# MOSFET_Connections.net
KiCad netlist of a schematic drawn in Altium Designer
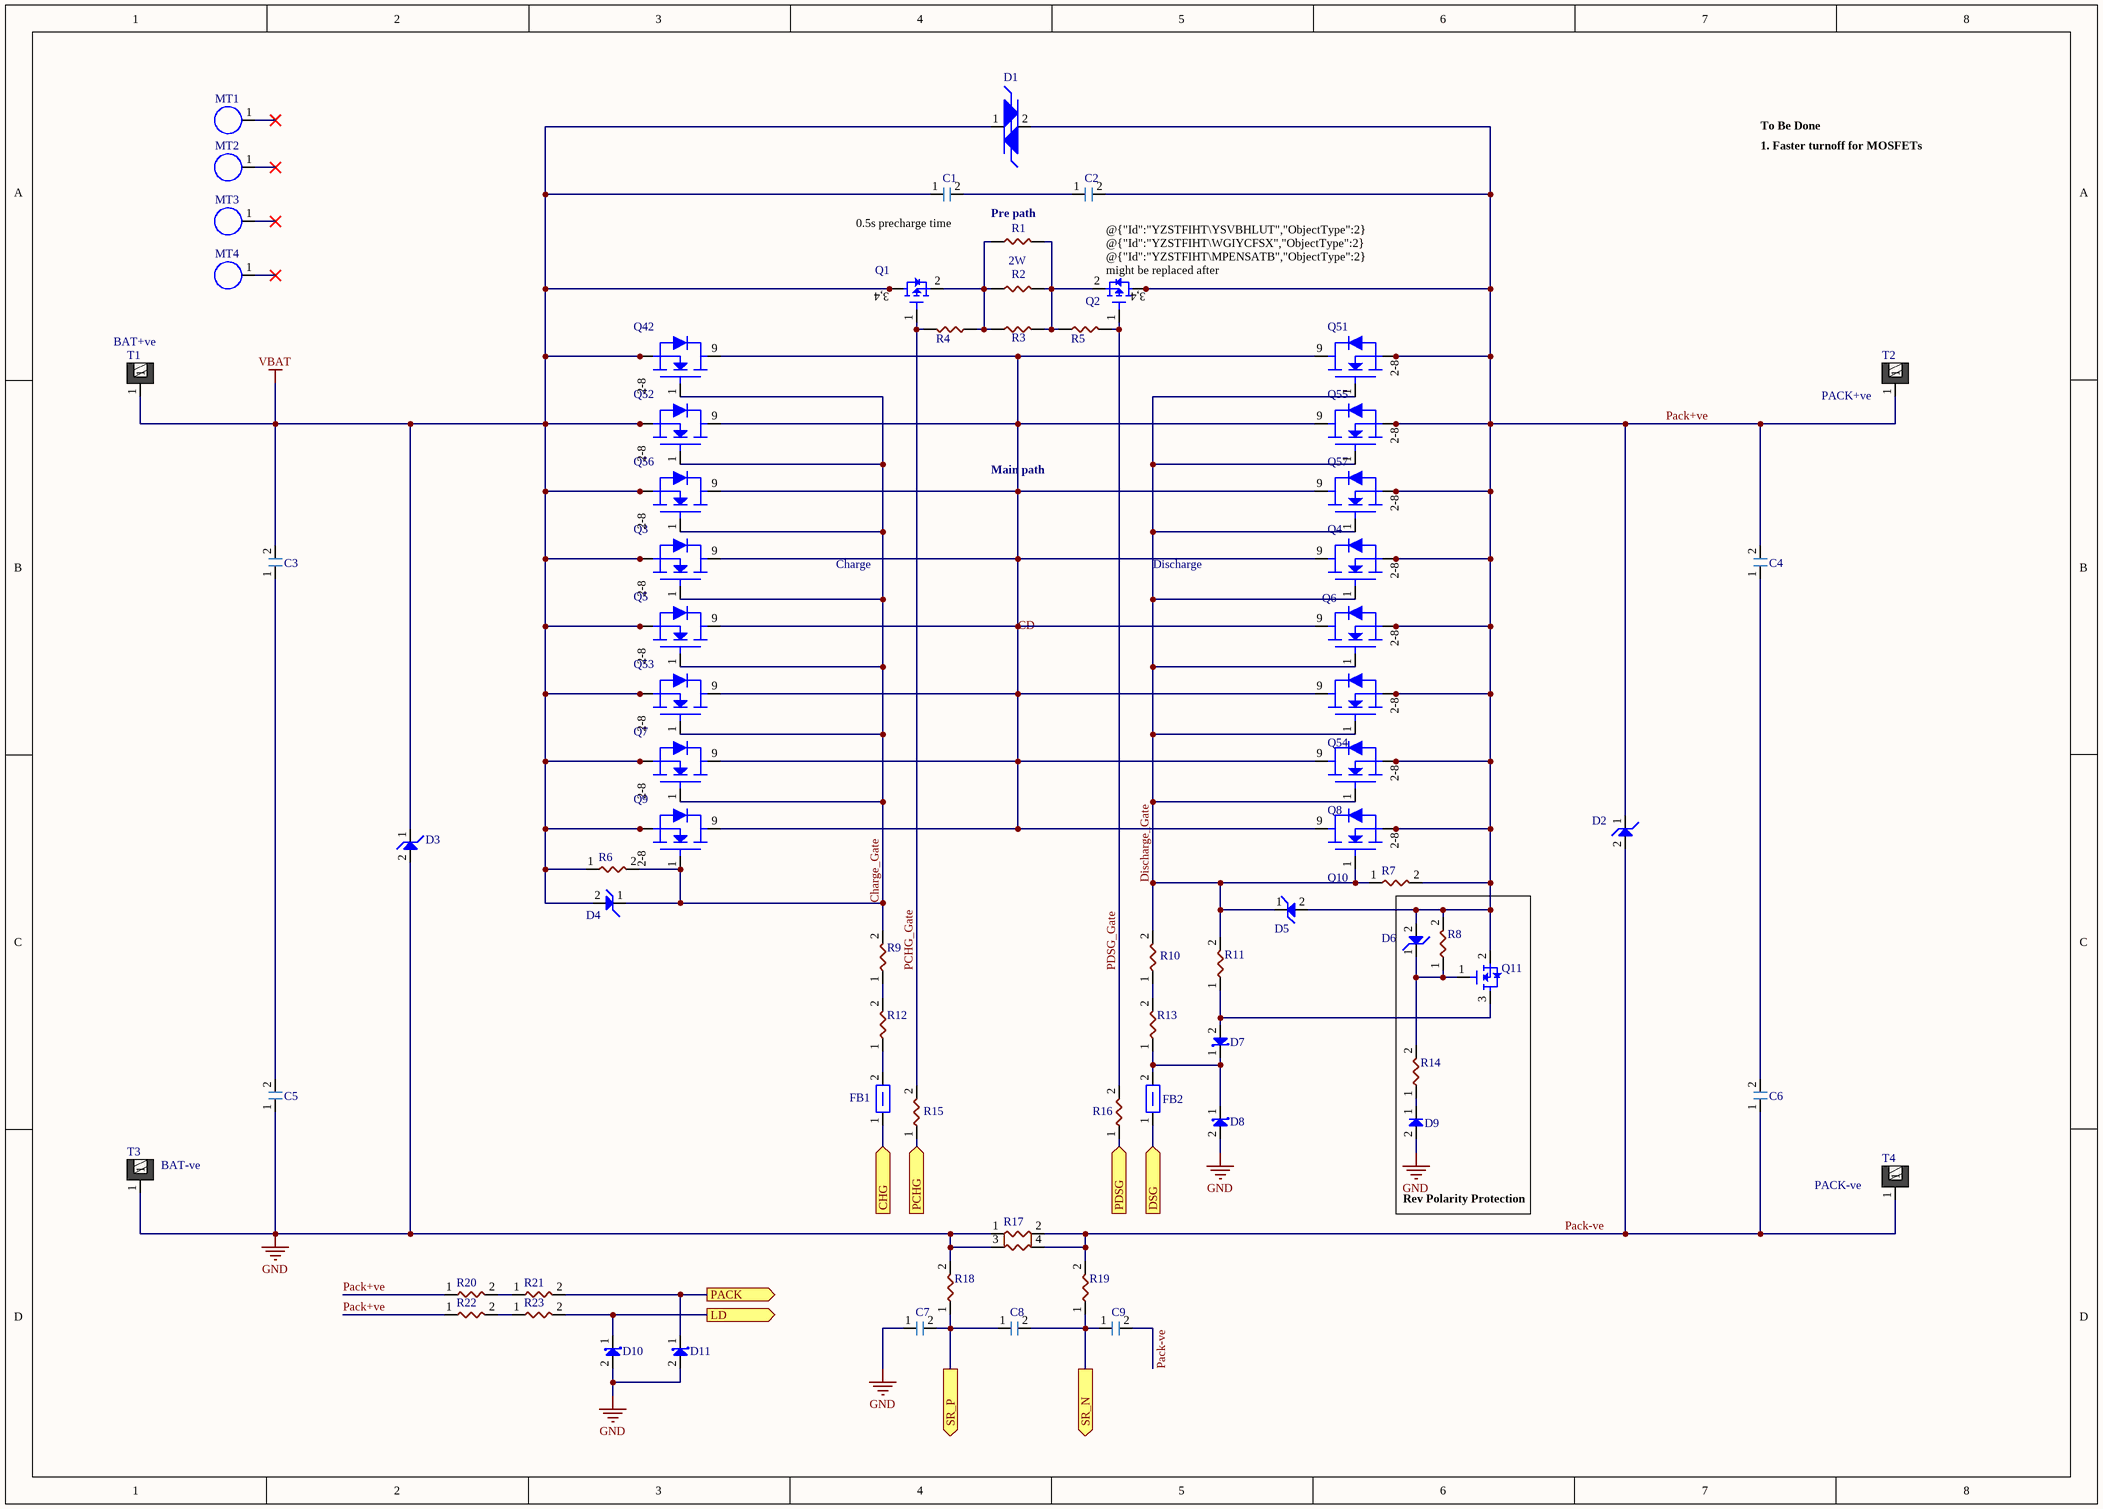
[diagram p0: MOSFET Connections.SchDoc]

(export (version "E")
  (design (tool "Eeschema 10.0.6"))
  (components
    (comp (ref "C1")
      (value "CC0603KRX7R0BB104")
      (footprint "CAPC1608X05N 0603")
      (description "Multilayer Ceramic Capacitor, 0.1uF, 100V, ±10%,  X7R 0603 [1608 Metric]")
      (fields (field (name "MANUFACTURER") "Yageo") (field (name "TOLERANCE") "10%"))
      (libsource (lib "BMS_V2.1_Adv") (part "Cap_CC0603KRX7R0BB104"))
    )
    (comp (ref "C2")
      (value "CC0603KRX7R0BB104")
      (footprint "CAPC1608X05N 0603")
      (description "Multilayer Ceramic Capacitor, 0.1uF, 100V, ±10%,  X7R 0603 [1608 Metric]")
      (fields (field (name "MANUFACTURER") "Yageo") (field (name "TOLERANCE") "10%"))
      (libsource (lib "BMS_V2.1_Adv") (part "Cap_CC0603KRX7R0BB104"))
    )
    (comp (ref "C3")
      (value "CC0603KRX7R0BB104")
      (footprint "CAPC1608X05N 0603")
      (description "Multilayer Ceramic Capacitor, 0.1uF, 100V, ±10%,  X7R 0603 [1608 Metric]")
      (fields (field (name "MANUFACTURER") "Yageo") (field (name "TOLERANCE") "10%"))
      (libsource (lib "BMS_V2.1_Adv") (part "Cap_CC0603KRX7R0BB104"))
    )
    (comp (ref "C4")
      (value "CC0603KRX7R0BB104")
      (footprint "CAPC1608X05N 0603")
      (description "Multilayer Ceramic Capacitor, 0.1uF, 100V, ±10%,  X7R 0603 [1608 Metric]")
      (fields (field (name "MANUFACTURER") "Yageo") (field (name "TOLERANCE") "10%"))
      (libsource (lib "BMS_V2.1_Adv") (part "Cap_CC0603KRX7R0BB104"))
    )
    (comp (ref "C5")
      (value "CC0603KRX7R0BB104")
      (footprint "CAPC1608X05N 0603")
      (description "Multilayer Ceramic Capacitor, 0.1uF, 100V, ±10%,  X7R 0603 [1608 Metric]")
      (fields (field (name "MANUFACTURER") "Yageo") (field (name "TOLERANCE") "10%"))
      (libsource (lib "BMS_V2.1_Adv") (part "Cap_CC0603KRX7R0BB104"))
    )
    (comp (ref "C6")
      (value "CC0603KRX7R0BB104")
      (footprint "CAPC1608X05N 0603")
      (description "Multilayer Ceramic Capacitor, 0.1uF, 100V, ±10%,  X7R 0603 [1608 Metric]")
      (fields (field (name "MANUFACTURER") "Yageo") (field (name "TOLERANCE") "10%"))
      (libsource (lib "BMS_V2.1_Adv") (part "Cap_CC0603KRX7R0BB104"))
    )
    (comp (ref "C7")
      (value "GRM188R72A104KA35D")
      (footprint "CAPC1608X05N 0603")
      (description "Multilayer Ceramic Capacitor, 100 nF, 100 V, ± 10%, X7R, 0603 [1608 Metric]")
      (fields (field (name "MANUFACTURER") "Murata") (field (name "TOLERANCE") "10%"))
      (libsource (lib "BMS_V2.1_Adv") (part "Cap_GRM188R72A104KA35D"))
    )
    (comp (ref "C8")
      (value "GRM188R72A104KA35D")
      (footprint "CAPC1608X05N 0603")
      (description "Multilayer Ceramic Capacitor, 100 nF, 100 V, ± 10%, X7R, 0603 [1608 Metric]")
      (fields (field (name "MANUFACTURER") "Murata") (field (name "TOLERANCE") "10%"))
      (libsource (lib "BMS_V2.1_Adv") (part "Cap_GRM188R72A104KA35D"))
    )
    (comp (ref "C9")
      (value "GRM188R72A104KA35D")
      (footprint "CAPC1608X05N 0603")
      (description "Multilayer Ceramic Capacitor, 100 nF, 100 V, ± 10%, X7R, 0603 [1608 Metric]")
      (fields (field (name "MANUFACTURER") "Murata") (field (name "TOLERANCE") "10%"))
      (libsource (lib "BMS_V2.1_Adv") (part "Cap_GRM188R72A104KA35D"))
    )
    (comp (ref "D1")
      (value "SMP100LC-140")
      (footprint "BMS_v2:DIODE_SMP100LC-140")
      (description "140V Off-State 400 A Ipp TVS Thyristor DO-214AA, SMB")
      (fields (field (name "MANUFACTURER") "ST") (field (name "VOLTAGE") "140V"))
      (libsource (lib "BMS_V2.1_Adv") (part "Diode_TVS_SMP100LC-140"))
    )
    (comp (ref "D2")
      (value "SMDJ70A")
      (footprint "DIODE_SMDJ70A")
      (description "113V Clamp 31A Ipp Tvs Diode Surface Mount DO-214AB (SMCJ)")
      (fields (field (name "MANUFACTURER") "LittleFuse") (field (name "POWER") "3kW (Peak)"))
      (libsource (lib "BMS_V2.1_Adv") (part "Diode_TVS_SMDJ70A"))
    )
    (comp (ref "D3")
      (value "SMDJ70A")
      (footprint "DIODE_SMDJ70A")
      (description "113V Clamp 31A Ipp Tvs Diode Surface Mount DO-214AB (SMCJ)")
      (fields (field (name "MANUFACTURER") "LittleFuse") (field (name "POWER") "3kW (Peak)"))
      (libsource (lib "BMS_V2.1_Adv") (part "Diode_TVS_SMDJ70A"))
    )
    (comp (ref "D4")
      (value "MMSZ5246BQ-7-F")
      (footprint "DIODE_SOD123")
      (description "Zener Diode 16 V 500 mW ±5% Surface Mount SOD-123")
      (fields (field (name "MANUFACTURER") "Diodes Inc.") (field (name "POWER") "370mW"))
      (libsource (lib "BMS_V2.1_Adv") (part "Diode_MMSZ5246BQ-7-F"))
    )
    (comp (ref "D5")
      (value "MMSZ5246BQ-7-F")
      (footprint "DIODE_SOD123")
      (description "Zener Diode 16 V 500 mW ±5% Surface Mount SOD-123")
      (fields (field (name "MANUFACTURER") "Diodes Inc.") (field (name "POWER") "370mW"))
      (libsource (lib "BMS_V2.1_Adv") (part "Diode_MMSZ5246BQ-7-F"))
    )
    (comp (ref "D6")
      (value "MMSZ5246BQ-7-F")
      (footprint "DIODE_SOD123")
      (description "Zener Diode 16 V 500 mW ±5% Surface Mount SOD-123")
      (fields (field (name "MANUFACTURER") "Diodes Inc.") (field (name "POWER") "370mW"))
      (libsource (lib "BMS_V2.1_Adv") (part "Diode_MMSZ5246BQ-7-F"))
    )
    (comp (ref "D7")
      (value "BAT46W-7-F")
      (footprint "DIODE_SOD123")
      (description "Diode 100 V 150mA Surface Mount SOD-123")
      (fields (field (name "MANUFACTURER") "Diodes Inc.") (field (name "POWER") "200mW"))
      (libsource (lib "BMS_V2.1_Adv") (part "Diode_BAT46W-7-F"))
    )
    (comp (ref "D8")
      (value "BAT46W-7-F")
      (footprint "DIODE_SOD123")
      (description "Diode 100 V 150mA Surface Mount SOD-123")
      (fields (field (name "MANUFACTURER") "Diodes Inc.") (field (name "POWER") "200mW"))
      (libsource (lib "BMS_V2.1_Adv") (part "Diode_BAT46W-7-F"))
    )
    (comp (ref "D9")
      (value "SBAS16HT1G")
      (footprint "DIODE_SOD323")
      (description "DIODE GEN PURP 100V 200MA SOD323")
      (fields (field (name "MANUFACTURER") "OnSemi") (field (name "VOLTAGE") "100V"))
      (libsource (lib "BMS_V2.1_Adv") (part "Diode_SBAS16HT1G"))
    )
    (comp (ref "D10")
      (value "BAT46W-7-F")
      (footprint "DIODE_SOD123")
      (description "Diode 100 V 150mA Surface Mount SOD-123")
      (fields (field (name "MANUFACTURER") "Diodes Inc.") (field (name "POWER") "200mW"))
      (libsource (lib "BMS_V2.1_Adv") (part "Diode_BAT46W-7-F"))
    )
    (comp (ref "D11")
      (value "BAT46W-7-F")
      (footprint "DIODE_SOD123")
      (description "Diode 100 V 150mA Surface Mount SOD-123")
      (fields (field (name "MANUFACTURER") "Diodes Inc.") (field (name "POWER") "200mW"))
      (libsource (lib "BMS_V2.1_Adv") (part "Diode_BAT46W-7-F"))
    )
    (comp (ref "FB1")
      (value "74279265")
      (footprint "RESC1608X05N 0603")
      (description "600 Ohms @ 100 MHz 1 Signal Line Ferrite Bead 0603 (1608 Metric) 200mA 450mOhm")
      (fields (field (name "MANUFACTURER") "Wurth Electronik"))
      (libsource (lib "BMS_V2.1_Adv") (part "FB_74279265"))
    )
    (comp (ref "FB2")
      (value "74279265")
      (footprint "RESC1608X05N 0603")
      (description "600 Ohms @ 100 MHz 1 Signal Line Ferrite Bead 0603 (1608 Metric) 200mA 450mOhm")
      (fields (field (name "MANUFACTURER") "Wurth Electronik"))
      (libsource (lib "BMS_V2.1_Adv") (part "FB_74279265"))
    )
    (comp (ref "MT1")
      (value "M3 Mounting Hole")
      (footprint "Mounting Hole")
      (libsource (lib "BMS_V2.1_Adv") (part "Mounting Hole M3"))
    )
    (comp (ref "MT2")
      (value "M3 Mounting Hole")
      (footprint "Mounting Hole")
      (libsource (lib "BMS_V2.1_Adv") (part "Mounting Hole M3"))
    )
    (comp (ref "MT3")
      (value "M3 Mounting Hole")
      (footprint "Mounting Hole")
      (libsource (lib "BMS_V2.1_Adv") (part "Mounting Hole M3"))
    )
    (comp (ref "MT4")
      (value "M3 Mounting Hole")
      (footprint "Mounting Hole")
      (libsource (lib "BMS_V2.1_Adv") (part "Mounting Hole M3"))
    )
    (comp (ref "Q1")
      (value "ZXMP10A17GQTA")
      (footprint "SOT230P700X180-4N")
      (description "P-Channel 100 V 2.4A (Ta) 2W (Ta) Surface Mount SOT-223-3")
      (fields (field (name "MANUFACTURER") "Diodes Inc.") (field (name "POWER") "2W"))
      (libsource (lib "BMS_V2.1_Adv") (part "FET_ZXMP10A17GQTA"))
    )
    (comp (ref "Q2")
      (value "ZXMP10A17GQTA")
      (footprint "SOT230P700X180-4N")
      (description "P-Channel 100 V 2.4A (Ta) 2W (Ta) Surface Mount SOT-223-3")
      (fields (field (name "MANUFACTURER") "Diodes Inc.") (field (name "POWER") "2W"))
      (libsource (lib "BMS_V2.1_Adv") (part "FET_ZXMP10A17GQTA"))
    )
    (comp (ref "Q3")
      (value "NVBLS0D8N08XTXG")
      (footprint "DPAK120P1168X240-9N")
      (description "N-Channel 80 V 457A (Tc) 325W (Tc) Surface Mount 8-HPSOF")
      (fields (field (name "MANUFACTURER") "OnSemi") (field (name "VOLTAGE") "80V"))
      (libsource (lib "BMS_V2.1_Adv") (part "FET_NVBLS0D8N08XTXG"))
    )
    (comp (ref "Q4")
      (value "NVBLS0D8N08XTXG")
      (footprint "DPAK120P1168X240-9N")
      (description "N-Channel 80 V 457A (Tc) 325W (Tc) Surface Mount 8-HPSOF")
      (fields (field (name "MANUFACTURER") "OnSemi") (field (name "VOLTAGE") "80V"))
      (libsource (lib "BMS_V2.1_Adv") (part "FET_NVBLS0D8N08XTXG"))
    )
    (comp (ref "Q5")
      (value "NVBLS0D8N08XTXG")
      (footprint "DPAK120P1168X240-9N")
      (description "N-Channel 80 V 457A (Tc) 325W (Tc) Surface Mount 8-HPSOF")
      (fields (field (name "MANUFACTURER") "OnSemi") (field (name "VOLTAGE") "80V"))
      (libsource (lib "BMS_V2.1_Adv") (part "FET_NVBLS0D8N08XTXG"))
    )
    (comp (ref "Q6")
      (value "NVBLS0D8N08XTXG")
      (footprint "DPAK120P1168X240-9N")
      (description "N-Channel 80 V 457A (Tc) 325W (Tc) Surface Mount 8-HPSOF")
      (fields (field (name "MANUFACTURER") "OnSemi") (field (name "VOLTAGE") "80V"))
      (libsource (lib "BMS_V2.1_Adv") (part "FET_NVBLS0D8N08XTXG"))
    )
    (comp (ref "Q7")
      (value "NVBLS0D8N08XTXG")
      (footprint "DPAK120P1168X240-9N")
      (description "N-Channel 80 V 457A (Tc) 325W (Tc) Surface Mount 8-HPSOF")
      (fields (field (name "MANUFACTURER") "OnSemi") (field (name "VOLTAGE") "80V"))
      (libsource (lib "BMS_V2.1_Adv") (part "FET_NVBLS0D8N08XTXG"))
    )
    (comp (ref "Q8")
      (value "NVBLS0D8N08XTXG")
      (footprint "DPAK120P1168X240-9N")
      (description "N-Channel 80 V 457A (Tc) 325W (Tc) Surface Mount 8-HPSOF")
      (fields (field (name "MANUFACTURER") "OnSemi") (field (name "VOLTAGE") "80V"))
      (libsource (lib "BMS_V2.1_Adv") (part "FET_NVBLS0D8N08XTXG"))
    )
    (comp (ref "Q9")
      (value "NVBLS0D8N08XTXG")
      (footprint "DPAK120P1168X240-9N")
      (description "N-Channel 80 V 457A (Tc) 325W (Tc) Surface Mount 8-HPSOF")
      (fields (field (name "MANUFACTURER") "OnSemi") (field (name "VOLTAGE") "80V"))
      (libsource (lib "BMS_V2.1_Adv") (part "FET_NVBLS0D8N08XTXG"))
    )
    (comp (ref "Q10")
      (value "NVBLS0D8N08XTXG")
      (footprint "DPAK120P1168X240-9N")
      (description "N-Channel 80 V 457A (Tc) 325W (Tc) Surface Mount 8-HPSOF")
      (fields (field (name "MANUFACTURER") "OnSemi") (field (name "VOLTAGE") "80V"))
      (libsource (lib "BMS_V2.1_Adv") (part "FET_NVBLS0D8N08XTXG"))
    )
    (comp (ref "Q11")
      (value "2N7002KW")
      (footprint "SOT65P210X110-3N")
      (description "N-Channel 60 V 310mA (Ta) 350mW (Ta) Surface Mount SOT-323")
      (fields (field (name "MANUFACTURER") "OnSemi") (field (name "POWER") "350mW"))
      (libsource (lib "BMS_V2.1_Adv") (part "FET_2N7002KW"))
    )
    (comp (ref "Q42")
      (value "NVBLS0D8N08XTXG")
      (footprint "DPAK120P1168X240-9N")
      (description "N-Channel 80 V 457A (Tc) 325W (Tc) Surface Mount 8-HPSOF")
      (fields (field (name "MANUFACTURER") "OnSemi") (field (name "VOLTAGE") "80V"))
      (libsource (lib "BMS_V2.1_Adv") (part "FET_NVBLS0D8N08XTXG"))
    )
    (comp (ref "Q51")
      (value "NVBLS0D8N08XTXG")
      (footprint "DPAK120P1168X240-9N")
      (description "N-Channel 80 V 457A (Tc) 325W (Tc) Surface Mount 8-HPSOF")
      (fields (field (name "MANUFACTURER") "OnSemi") (field (name "VOLTAGE") "80V"))
      (libsource (lib "BMS_V2.1_Adv") (part "FET_NVBLS0D8N08XTXG"))
    )
    (comp (ref "Q52")
      (value "NVBLS0D8N08XTXG")
      (footprint "DPAK120P1168X240-9N")
      (description "N-Channel 80 V 457A (Tc) 325W (Tc) Surface Mount 8-HPSOF")
      (fields (field (name "MANUFACTURER") "OnSemi") (field (name "VOLTAGE") "80V"))
      (libsource (lib "BMS_V2.1_Adv") (part "FET_NVBLS0D8N08XTXG"))
    )
    (comp (ref "Q53")
      (value "NVBLS0D8N08XTXG")
      (footprint "DPAK120P1168X240-9N")
      (description "N-Channel 80 V 457A (Tc) 325W (Tc) Surface Mount 8-HPSOF")
      (fields (field (name "MANUFACTURER") "OnSemi") (field (name "VOLTAGE") "80V"))
      (libsource (lib "BMS_V2.1_Adv") (part "FET_NVBLS0D8N08XTXG"))
    )
    (comp (ref "Q54")
      (value "NVBLS0D8N08XTXG")
      (footprint "DPAK120P1168X240-9N")
      (description "N-Channel 80 V 457A (Tc) 325W (Tc) Surface Mount 8-HPSOF")
      (fields (field (name "MANUFACTURER") "OnSemi") (field (name "VOLTAGE") "80V"))
      (libsource (lib "BMS_V2.1_Adv") (part "FET_NVBLS0D8N08XTXG"))
    )
    (comp (ref "Q55")
      (value "NVBLS0D8N08XTXG")
      (footprint "DPAK120P1168X240-9N")
      (description "N-Channel 80 V 457A (Tc) 325W (Tc) Surface Mount 8-HPSOF")
      (fields (field (name "MANUFACTURER") "OnSemi") (field (name "VOLTAGE") "80V"))
      (libsource (lib "BMS_V2.1_Adv") (part "FET_NVBLS0D8N08XTXG"))
    )
    (comp (ref "Q56")
      (value "NVBLS0D8N08XTXG")
      (footprint "DPAK120P1168X240-9N")
      (description "N-Channel 80 V 457A (Tc) 325W (Tc) Surface Mount 8-HPSOF")
      (fields (field (name "MANUFACTURER") "OnSemi") (field (name "VOLTAGE") "80V"))
      (libsource (lib "BMS_V2.1_Adv") (part "FET_NVBLS0D8N08XTXG"))
    )
    (comp (ref "Q57")
      (value "NVBLS0D8N08XTXG")
      (footprint "DPAK120P1168X240-9N")
      (description "N-Channel 80 V 457A (Tc) 325W (Tc) Surface Mount 8-HPSOF")
      (fields (field (name "MANUFACTURER") "OnSemi") (field (name "VOLTAGE") "80V"))
      (libsource (lib "BMS_V2.1_Adv") (part "FET_NVBLS0D8N08XTXG"))
    )
    (comp (ref "R1")
      (value "AC2512FK-7W200RL")
      (footprint "RESC6332X07N 2512")
      (fields
        (field (name "MANUFACTURER") "Yageo")
        (field (name "POWER") "2W")
        (field (name "TOLERANCE") "1%")
      )
      (libsource (lib "BMS_V2.1_Adv") (part "Res_AC2512FK-7W200RL"))
    )
    (comp (ref "R2")
      (value "AC2512FK-7W200RL")
      (footprint "RESC6332X07N 2512")
      (fields
        (field (name "MANUFACTURER") "Yageo")
        (field (name "POWER") "2W")
        (field (name "TOLERANCE") "1%")
      )
      (libsource (lib "BMS_V2.1_Adv") (part "Res_AC2512FK-7W200RL"))
    )
    (comp (ref "R3")
      (value "AC2512FK-7W200RL")
      (footprint "RESC6332X07N 2512")
      (fields
        (field (name "MANUFACTURER") "Yageo")
        (field (name "POWER") "2W")
        (field (name "TOLERANCE") "1%")
      )
      (libsource (lib "BMS_V2.1_Adv") (part "Res_AC2512FK-7W200RL"))
    )
    (comp (ref "R4")
      (value "CRCW060310M0JNEA")
      (footprint "RESC1608X05N 0603")
      (description "SMD Chip Resistor, 10 MOhm,±5%, 100 mW, 0603 [1608 Metric], Thick Film, General Purpose")
      (fields (field (name "MANUFACTURER") "Vishay Dale") (field (name "POWER") "1/10W"))
      (libsource (lib "") (part "Res_CRCW060310M0JNEA_1"))
    )
    (comp (ref "R5")
      (value "CRCW060310M0JNEA")
      (footprint "RESC1608X05N 0603")
      (description "SMD Chip Resistor, 10 MOhm,±5%, 100 mW, 0603 [1608 Metric], Thick Film, General Purpose")
      (fields (field (name "MANUFACTURER") "Vishay Dale") (field (name "POWER") "1/10W"))
      (libsource (lib "") (part "Res_CRCW060310M0JNEA_1"))
    )
    (comp (ref "R6")
      (value "CRCW060310M0JNEA")
      (footprint "RESC1608X05N 0603")
      (description "SMD Chip Resistor, 10 MOhm,±5%, 100 mW, 0603 [1608 Metric], Thick Film, General Purpose")
      (fields (field (name "MANUFACTURER") "Vishay Dale") (field (name "POWER") "1/10W"))
      (libsource (lib "BMS_V2.1_Adv") (part "Res_CRCW060310M0JNEA"))
    )
    (comp (ref "R7")
      (value "CRCW060310M0JNEA")
      (footprint "RESC1608X05N 0603")
      (description "SMD Chip Resistor, 10 MOhm,±5%, 100 mW, 0603 [1608 Metric], Thick Film, General Purpose")
      (fields (field (name "MANUFACTURER") "Vishay Dale") (field (name "POWER") "1/10W"))
      (libsource (lib "BMS_V2.1_Adv") (part "Res_CRCW060310M0JNEA"))
    )
    (comp (ref "R8")
      (value "CRCW060310M0JNEA")
      (footprint "RESC1608X05N 0603")
      (description "SMD Chip Resistor, 10 MOhm,±5%, 100 mW, 0603 [1608 Metric], Thick Film, General Purpose")
      (fields (field (name "MANUFACTURER") "Vishay Dale") (field (name "POWER") "1/10W"))
      (libsource (lib "BMS_V2.1_Adv") (part "Res_CRCW060310M0JNEA"))
    )
    (comp (ref "R9")
      (value "CRCW06035K10JNEA")
      (footprint "RESC1608X05N 0603")
      (description "SMD Chip Resistor, 5.1k Ohm, ± 5%, 250 mW, 0603 [1608 Metric], Thick Film, General Purpose")
      (fields (field (name "MANUFACTURER") "Vishay Dale") (field (name "POWER") "1/10W"))
      (libsource (lib "BMS_V2.1_Adv") (part "Res_CRCW06035K10JNEA"))
    )
    (comp (ref "R10")
      (value "CRCW06035K10JNEA")
      (footprint "RESC1608X05N 0603")
      (description "SMD Chip Resistor, 5.1k Ohm, ± 5%, 250 mW, 0603 [1608 Metric], Thick Film, General Purpose")
      (fields (field (name "MANUFACTURER") "Vishay Dale") (field (name "POWER") "1/10W"))
      (libsource (lib "BMS_V2.1_Adv") (part "Res_CRCW06035K10JNEA"))
    )
    (comp (ref "R11")
      (value "CRCW06035K10JNEA")
      (footprint "RESC1608X05N 0603")
      (description "SMD Chip Resistor, 5.1k Ohm, ± 5%, 250 mW, 0603 [1608 Metric], Thick Film, General Purpose")
      (fields (field (name "MANUFACTURER") "Vishay Dale") (field (name "POWER") "1/10W"))
      (libsource (lib "BMS_V2.1_Adv") (part "Res_CRCW06035K10JNEA"))
    )
    (comp (ref "R12")
      (value "CRCW06035K10JNEA")
      (footprint "RESC1608X05N 0603")
      (description "SMD Chip Resistor, 5.1k Ohm, ± 5%, 250 mW, 0603 [1608 Metric], Thick Film, General Purpose")
      (fields (field (name "MANUFACTURER") "Vishay Dale") (field (name "POWER") "1/10W"))
      (libsource (lib "BMS_V2.1_Adv") (part "Res_CRCW06035K10JNEA"))
    )
    (comp (ref "R13")
      (value "CRCW06035K10JNEA")
      (footprint "RESC1608X05N 0603")
      (description "SMD Chip Resistor, 5.1k Ohm, ± 5%, 250 mW, 0603 [1608 Metric], Thick Film, General Purpose")
      (fields (field (name "MANUFACTURER") "Vishay Dale") (field (name "POWER") "1/10W"))
      (libsource (lib "BMS_V2.1_Adv") (part "Res_CRCW06035K10JNEA"))
    )
    (comp (ref "R14")
      (value "CRCW060310K0FKEA")
      (footprint "RESC1608X05N 0603")
      (description "SMD Chip Resistor, 10 kOhm,±1%, 100 mW, 0603 [1608 Metric], Thick Film, General Purpose")
      (fields (field (name "MANUFACTURER") "Vishay Dale") (field (name "POWER") "1/10W"))
      (libsource (lib "BMS_V2.1_Adv") (part "Res_CRCW060310K0FKEA"))
    )
    (comp (ref "R15")
      (value "CRCW06035K10JNEA")
      (footprint "RESC1608X05N 0603")
      (description "SMD Chip Resistor, 5.1k Ohm, ± 5%, 250 mW, 0603 [1608 Metric], Thick Film, General Purpose")
      (fields (field (name "MANUFACTURER") "Vishay Dale") (field (name "POWER") "1/10W"))
      (libsource (lib "BMS_V2.1_Adv") (part "Res_CRCW06035K10JNEA"))
    )
    (comp (ref "R16")
      (value "CRCW06035K10JNEA")
      (footprint "RESC1608X05N 0603")
      (description "SMD Chip Resistor, 5.1k Ohm, ± 5%, 250 mW, 0603 [1608 Metric], Thick Film, General Purpose")
      (fields (field (name "MANUFACTURER") "Vishay Dale") (field (name "POWER") "1/10W"))
      (libsource (lib "BMS_V2.1_Adv") (part "Res_CRCW06035K10JNEA"))
    )
    (comp (ref "R17")
      (value "WSLP2726L5000FEA")
      (footprint "WSLP2726-X- NS")
      (fields
        (field (name "MANUFACTURER") "Vishay Dale")
        (field (name "POWER") "7W")
        (field (name "TOLERANCE") "1%")
      )
      (libsource (lib "BMS_V2.1_Adv") (part "Res_WSLP2726L5000FEA"))
    )
    (comp (ref "R18")
      (value "AF0603FR-07100RL")
      (footprint "RESC1608X05N 0603")
      (fields
        (field (name "TOLERANCE") "1%")
        (field (name "MANUFACTURER") "Yageo")
        (field (name "POWER") "1/10W")
      )
      (libsource (lib "BMS_V2.1_Adv") (part "Res_AF0603FR-07100RL"))
    )
    (comp (ref "R19")
      (value "AF0603FR-07100RL")
      (footprint "RESC1608X05N 0603")
      (fields
        (field (name "TOLERANCE") "1%")
        (field (name "MANUFACTURER") "Yageo")
        (field (name "POWER") "1/10W")
      )
      (libsource (lib "BMS_V2.1_Adv") (part "Res_AF0603FR-07100RL"))
    )
    (comp (ref "R20")
      (value "CRCW12065K10JNEA")
      (footprint "RESC3216X06N 1206")
      (description "SMD Chip Resistor, 5.1k Ohm, ± 5%, 250 mW, 1206 [3216 Metric], Thick Film, General Purpose")
      (fields (field (name "MANUFACTURER") "Vishay Dale") (field (name "POWER") "1/4W"))
      (libsource (lib "BMS_V2.1_Adv") (part "Res_CRCW12065K10JNEA"))
    )
    (comp (ref "R21")
      (value "CRCW12065K10JNEA")
      (footprint "RESC3216X06N 1206")
      (description "SMD Chip Resistor, 5.1k Ohm, ± 5%, 250 mW, 1206 [3216 Metric], Thick Film, General Purpose")
      (fields (field (name "MANUFACTURER") "Vishay Dale") (field (name "POWER") "1/4W"))
      (libsource (lib "BMS_V2.1_Adv") (part "Res_CRCW12065K10JNEA"))
    )
    (comp (ref "R22")
      (value "CRCW12065K10JNEA")
      (footprint "RESC3216X06N 1206")
      (description "SMD Chip Resistor, 5.1k Ohm, ± 5%, 250 mW, 1206 [3216 Metric], Thick Film, General Purpose")
      (fields (field (name "MANUFACTURER") "Vishay Dale") (field (name "POWER") "1/4W"))
      (libsource (lib "BMS_V2.1_Adv") (part "Res_CRCW12065K10JNEA"))
    )
    (comp (ref "R23")
      (value "CRCW12065K10JNEA")
      (footprint "RESC3216X06N 1206")
      (description "SMD Chip Resistor, 5.1k Ohm, ± 5%, 250 mW, 1206 [3216 Metric], Thick Film, General Purpose")
      (fields (field (name "MANUFACTURER") "Vishay Dale") (field (name "POWER") "1/4W"))
      (libsource (lib "BMS_V2.1_Adv") (part "Res_CRCW12065K10JNEA"))
    )
    (comp (ref "T1")
      (value "7461057")
      (footprint "7461057")
      (description "6 Pin Screw Terminal, Power Tap M3 Through Hole")
      (fields (field (name "MANUFACTURER") "Wurth Electronik"))
      (libsource (lib "BMS_V2.1_Adv") (part "Terminal_7461057"))
    )
    (comp (ref "T2")
      (value "7461057")
      (footprint "7461057")
      (description "6 Pin Screw Terminal, Power Tap M3 Through Hole")
      (fields (field (name "MANUFACTURER") "Wurth Electronik"))
      (libsource (lib "BMS_V2.1_Adv") (part "Terminal_7461057"))
    )
    (comp (ref "T3")
      (value "7461057")
      (footprint "7461057")
      (description "6 Pin Screw Terminal, Power Tap M3 Through Hole")
      (fields (field (name "MANUFACTURER") "Wurth Electronik"))
      (libsource (lib "BMS_V2.1_Adv") (part "Terminal_7461057"))
    )
    (comp (ref "T4")
      (value "7461057")
      (footprint "7461057")
      (description "6 Pin Screw Terminal, Power Tap M3 Through Hole")
      (fields (field (name "MANUFACTURER") "Wurth Electronik"))
      (libsource (lib "BMS_V2.1_Adv") (part "Terminal_7461057"))
    )
  )
  (nets
    (net (code "1") (name "/CD") (class "Default")
      (node (ref "Q10") (pin "9") (pinfunction "Drain_9") (pintype "passive"))
      (node (ref "Q3") (pin "9") (pinfunction "Drain_9") (pintype "passive"))
      (node (ref "Q4") (pin "9") (pinfunction "Drain_9") (pintype "passive"))
      (node (ref "Q42") (pin "9") (pinfunction "Drain_9") (pintype "passive"))
      (node (ref "Q5") (pin "9") (pinfunction "Drain_9") (pintype "passive"))
      (node (ref "Q51") (pin "9") (pinfunction "Drain_9") (pintype "passive"))
      (node (ref "Q52") (pin "9") (pinfunction "Drain_9") (pintype "passive"))
      (node (ref "Q53") (pin "9") (pinfunction "Drain_9") (pintype "passive"))
      (node (ref "Q54") (pin "9") (pinfunction "Drain_9") (pintype "passive"))
      (node (ref "Q55") (pin "9") (pinfunction "Drain_9") (pintype "passive"))
      (node (ref "Q56") (pin "9") (pinfunction "Drain_9") (pintype "passive"))
      (node (ref "Q57") (pin "9") (pinfunction "Drain_9") (pintype "passive"))
      (node (ref "Q6") (pin "9") (pinfunction "Drain_9") (pintype "passive"))
      (node (ref "Q7") (pin "9") (pinfunction "Drain_9") (pintype "passive"))
      (node (ref "Q8") (pin "9") (pinfunction "Drain_9") (pintype "passive"))
      (node (ref "Q9") (pin "9") (pinfunction "Drain_9") (pintype "passive"))
    )
    (net (code "2") (name "/CHG") (class "Default")
      (node (ref "FB1") (pin "1") (pinfunction "1_1") (pintype "passive"))
    )
    (net (code "3") (name "/Charge_Gate") (class "Default")
      (node (ref "D4") (pin "1") (pinfunction "Cathode_1") (pintype "passive"))
      (node (ref "Q3") (pin "1") (pinfunction "Gate_1") (pintype "passive"))
      (node (ref "Q42") (pin "1") (pinfunction "Gate_1") (pintype "passive"))
      (node (ref "Q5") (pin "1") (pinfunction "Gate_1") (pintype "passive"))
      (node (ref "Q52") (pin "1") (pinfunction "Gate_1") (pintype "passive"))
      (node (ref "Q53") (pin "1") (pinfunction "Gate_1") (pintype "passive"))
      (node (ref "Q56") (pin "1") (pinfunction "Gate_1") (pintype "passive"))
      (node (ref "Q7") (pin "1") (pinfunction "Gate_1") (pintype "passive"))
      (node (ref "Q9") (pin "1") (pinfunction "Gate_1") (pintype "passive"))
      (node (ref "R6") (pin "2") (pinfunction "2_2") (pintype "passive"))
      (node (ref "R9") (pin "2") (pinfunction "2_2") (pintype "passive"))
    )
    (net (code "4") (name "/DSG") (class "Default")
      (node (ref "FB2") (pin "1") (pinfunction "1_1") (pintype "passive"))
    )
    (net (code "5") (name "/Discharge_Gate") (class "Default")
      (node (ref "D5") (pin "1") (pinfunction "Cathode_1") (pintype "passive"))
      (node (ref "Q10") (pin "1") (pinfunction "Gate_1") (pintype "passive"))
      (node (ref "Q4") (pin "1") (pinfunction "Gate_1") (pintype "passive"))
      (node (ref "Q51") (pin "1") (pinfunction "Gate_1") (pintype "passive"))
      (node (ref "Q54") (pin "1") (pinfunction "Gate_1") (pintype "passive"))
      (node (ref "Q55") (pin "1") (pinfunction "Gate_1") (pintype "passive"))
      (node (ref "Q57") (pin "1") (pinfunction "Gate_1") (pintype "passive"))
      (node (ref "Q6") (pin "1") (pinfunction "Gate_1") (pintype "passive"))
      (node (ref "Q8") (pin "1") (pinfunction "Gate_1") (pintype "passive"))
      (node (ref "R10") (pin "2") (pinfunction "2_2") (pintype "passive"))
      (node (ref "R11") (pin "2") (pinfunction "2_2") (pintype "passive"))
      (node (ref "R7") (pin "1") (pinfunction "1_1") (pintype "passive"))
    )
    (net (code "6") (name "/LD") (class "Default")
      (node (ref "D10") (pin "1") (pinfunction "Cathode_1") (pintype "passive"))
      (node (ref "R23") (pin "2") (pinfunction "2_2") (pintype "passive"))
    )
    (net (code "7") (name "/PACK") (class "Default")
      (node (ref "D11") (pin "1") (pinfunction "Cathode_1") (pintype "passive"))
      (node (ref "R21") (pin "2") (pinfunction "2_2") (pintype "passive"))
    )
    (net (code "8") (name "/PCHG") (class "Default")
      (node (ref "R15") (pin "1") (pinfunction "1_1") (pintype "passive"))
    )
    (net (code "9") (name "/PCHG_Gate") (class "Default")
      (node (ref "Q1") (pin "1") (pinfunction "Gate_1") (pintype "passive"))
      (node (ref "R15") (pin "2") (pinfunction "2_2") (pintype "passive"))
      (node (ref "R4") (pin "2") (pinfunction "2_2") (pintype "passive"))
    )
    (net (code "10") (name "/PDSG") (class "Default")
      (node (ref "R16") (pin "1") (pinfunction "1_1") (pintype "passive"))
    )
    (net (code "11") (name "/PDSG_Gate") (class "Default")
      (node (ref "Q2") (pin "1") (pinfunction "Gate_1") (pintype "passive"))
      (node (ref "R16") (pin "2") (pinfunction "2_2") (pintype "passive"))
      (node (ref "R5") (pin "2") (pinfunction "2_2") (pintype "passive"))
    )
    (net (code "12") (name "/Pack+ve") (class "Default")
      (node (ref "C2") (pin "2") (pinfunction "2_2") (pintype "passive"))
      (node (ref "C4") (pin "2") (pinfunction "2_2") (pintype "passive"))
      (node (ref "D1") (pin "2") (pinfunction "2_2") (pintype "passive"))
      (node (ref "D2") (pin "1") (pinfunction "Cathode_1") (pintype "passive"))
      (node (ref "D5") (pin "2") (pinfunction "Anode_2") (pintype "passive"))
      (node (ref "D6") (pin "2") (pinfunction "Anode_2") (pintype "passive"))
      (node (ref "Q10") (pin "2") (pinfunction "Source_2") (pintype "passive"))
      (node (ref "Q10") (pin "3") (pinfunction "Source_3") (pintype "passive"))
      (node (ref "Q10") (pin "4") (pinfunction "Source_4") (pintype "passive"))
      (node (ref "Q10") (pin "5") (pinfunction "Source_5") (pintype "passive"))
      (node (ref "Q10") (pin "6") (pinfunction "Source_6") (pintype "passive"))
      (node (ref "Q10") (pin "7") (pinfunction "Source_7") (pintype "passive"))
      (node (ref "Q10") (pin "8") (pinfunction "Source_8") (pintype "passive"))
      (node (ref "Q11") (pin "2") (pinfunction "Source_2") (pintype "passive"))
      (node (ref "Q2") (pin "3") (pinfunction "Drain_3") (pintype "passive"))
      (node (ref "Q2") (pin "4") (pinfunction "Drain_4") (pintype "passive"))
      (node (ref "Q4") (pin "2") (pinfunction "Source_2") (pintype "passive"))
      (node (ref "Q4") (pin "3") (pinfunction "Source_3") (pintype "passive"))
      (node (ref "Q4") (pin "4") (pinfunction "Source_4") (pintype "passive"))
      (node (ref "Q4") (pin "5") (pinfunction "Source_5") (pintype "passive"))
      (node (ref "Q4") (pin "6") (pinfunction "Source_6") (pintype "passive"))
      (node (ref "Q4") (pin "7") (pinfunction "Source_7") (pintype "passive"))
      (node (ref "Q4") (pin "8") (pinfunction "Source_8") (pintype "passive"))
      (node (ref "Q51") (pin "2") (pinfunction "Source_2") (pintype "passive"))
      (node (ref "Q51") (pin "3") (pinfunction "Source_3") (pintype "passive"))
      (node (ref "Q51") (pin "4") (pinfunction "Source_4") (pintype "passive"))
      (node (ref "Q51") (pin "5") (pinfunction "Source_5") (pintype "passive"))
      (node (ref "Q51") (pin "6") (pinfunction "Source_6") (pintype "passive"))
      (node (ref "Q51") (pin "7") (pinfunction "Source_7") (pintype "passive"))
      (node (ref "Q51") (pin "8") (pinfunction "Source_8") (pintype "passive"))
      (node (ref "Q54") (pin "2") (pinfunction "Source_2") (pintype "passive"))
      (node (ref "Q54") (pin "3") (pinfunction "Source_3") (pintype "passive"))
      (node (ref "Q54") (pin "4") (pinfunction "Source_4") (pintype "passive"))
      (node (ref "Q54") (pin "5") (pinfunction "Source_5") (pintype "passive"))
      (node (ref "Q54") (pin "6") (pinfunction "Source_6") (pintype "passive"))
      (node (ref "Q54") (pin "7") (pinfunction "Source_7") (pintype "passive"))
      (node (ref "Q54") (pin "8") (pinfunction "Source_8") (pintype "passive"))
      (node (ref "Q55") (pin "2") (pinfunction "Source_2") (pintype "passive"))
      (node (ref "Q55") (pin "3") (pinfunction "Source_3") (pintype "passive"))
      (node (ref "Q55") (pin "4") (pinfunction "Source_4") (pintype "passive"))
      (node (ref "Q55") (pin "5") (pinfunction "Source_5") (pintype "passive"))
      (node (ref "Q55") (pin "6") (pinfunction "Source_6") (pintype "passive"))
      (node (ref "Q55") (pin "7") (pinfunction "Source_7") (pintype "passive"))
      (node (ref "Q55") (pin "8") (pinfunction "Source_8") (pintype "passive"))
      (node (ref "Q57") (pin "2") (pinfunction "Source_2") (pintype "passive"))
      (node (ref "Q57") (pin "3") (pinfunction "Source_3") (pintype "passive"))
      (node (ref "Q57") (pin "4") (pinfunction "Source_4") (pintype "passive"))
      (node (ref "Q57") (pin "5") (pinfunction "Source_5") (pintype "passive"))
      (node (ref "Q57") (pin "6") (pinfunction "Source_6") (pintype "passive"))
      (node (ref "Q57") (pin "7") (pinfunction "Source_7") (pintype "passive"))
      (node (ref "Q57") (pin "8") (pinfunction "Source_8") (pintype "passive"))
      (node (ref "Q6") (pin "2") (pinfunction "Source_2") (pintype "passive"))
      (node (ref "Q6") (pin "3") (pinfunction "Source_3") (pintype "passive"))
      (node (ref "Q6") (pin "4") (pinfunction "Source_4") (pintype "passive"))
      (node (ref "Q6") (pin "5") (pinfunction "Source_5") (pintype "passive"))
      (node (ref "Q6") (pin "6") (pinfunction "Source_6") (pintype "passive"))
      (node (ref "Q6") (pin "7") (pinfunction "Source_7") (pintype "passive"))
      (node (ref "Q6") (pin "8") (pinfunction "Source_8") (pintype "passive"))
      (node (ref "Q8") (pin "2") (pinfunction "Source_2") (pintype "passive"))
      (node (ref "Q8") (pin "3") (pinfunction "Source_3") (pintype "passive"))
      (node (ref "Q8") (pin "4") (pinfunction "Source_4") (pintype "passive"))
      (node (ref "Q8") (pin "5") (pinfunction "Source_5") (pintype "passive"))
      (node (ref "Q8") (pin "6") (pinfunction "Source_6") (pintype "passive"))
      (node (ref "Q8") (pin "7") (pinfunction "Source_7") (pintype "passive"))
      (node (ref "Q8") (pin "8") (pinfunction "Source_8") (pintype "passive"))
      (node (ref "R20") (pin "1") (pinfunction "1_1") (pintype "passive"))
      (node (ref "R22") (pin "1") (pinfunction "1_1") (pintype "passive"))
      (node (ref "R7") (pin "2") (pinfunction "2_2") (pintype "passive"))
      (node (ref "R8") (pin "2") (pinfunction "2_2") (pintype "passive"))
      (node (ref "T2") (pin "1") (pinfunction "1_1") (pintype "passive"))
    )
    (net (code "13") (name "/Pack-ve") (class "Default")
      (node (ref "C6") (pin "1") (pinfunction "1_1") (pintype "passive"))
      (node (ref "C9") (pin "2") (pinfunction "2_2") (pintype "passive"))
      (node (ref "D2") (pin "2") (pinfunction "Anode_2") (pintype "passive"))
      (node (ref "R17") (pin "2") (pinfunction "2_2") (pintype "passive"))
      (node (ref "R17") (pin "4") (pinfunction "4_4") (pintype "passive"))
      (node (ref "R19") (pin "2") (pinfunction "2_2") (pintype "passive"))
      (node (ref "T4") (pin "1") (pinfunction "1_1") (pintype "passive"))
    )
    (net (code "14") (name "/SR_N") (class "Default")
      (node (ref "C8") (pin "2") (pinfunction "2_2") (pintype "passive"))
      (node (ref "C9") (pin "1") (pinfunction "1_1") (pintype "passive"))
      (node (ref "R19") (pin "1") (pinfunction "1_1") (pintype "passive"))
    )
    (net (code "15") (name "/SR_P") (class "Default")
      (node (ref "C7") (pin "2") (pinfunction "2_2") (pintype "passive"))
      (node (ref "C8") (pin "1") (pinfunction "1_1") (pintype "passive"))
      (node (ref "R18") (pin "1") (pinfunction "1_1") (pintype "passive"))
    )
    (net (code "16") (name "GND") (class "Default")
      (node (ref "C5") (pin "1") (pinfunction "1_1") (pintype "passive"))
      (node (ref "C7") (pin "1") (pinfunction "1_1") (pintype "passive"))
      (node (ref "D10") (pin "2") (pinfunction "Anode_2") (pintype "passive"))
      (node (ref "D11") (pin "2") (pinfunction "Anode_2") (pintype "passive"))
      (node (ref "D3") (pin "2") (pinfunction "Anode_2") (pintype "passive"))
      (node (ref "D8") (pin "2") (pinfunction "Anode_2") (pintype "passive"))
      (node (ref "D9") (pin "2") (pinfunction "Anode_2") (pintype "passive"))
      (node (ref "R17") (pin "1") (pinfunction "1_1") (pintype "passive"))
      (node (ref "R17") (pin "3") (pinfunction "3_3") (pintype "passive"))
      (node (ref "R18") (pin "2") (pinfunction "2_2") (pintype "passive"))
      (node (ref "T3") (pin "1") (pinfunction "1_1") (pintype "passive"))
    )
    (net (code "17") (name "Net-(C1-Pad2)") (class "Default")
      (node (ref "C1") (pin "2") (pinfunction "2_2") (pintype "passive"))
      (node (ref "C2") (pin "1") (pinfunction "1_1") (pintype "passive"))
    )
    (net (code "18") (name "Net-(C3-Pad1)") (class "Default")
      (node (ref "C3") (pin "1") (pinfunction "1_1") (pintype "passive"))
      (node (ref "C5") (pin "2") (pinfunction "2_2") (pintype "passive"))
    )
    (net (code "19") (name "Net-(C4-Pad1)") (class "Default")
      (node (ref "C4") (pin "1") (pinfunction "1_1") (pintype "passive"))
      (node (ref "C6") (pin "2") (pinfunction "2_2") (pintype "passive"))
    )
    (net (code "20") (name "Net-(D6-Cathode)") (class "Default")
      (node (ref "D6") (pin "1") (pinfunction "Cathode_1") (pintype "passive"))
      (node (ref "Q11") (pin "1") (pinfunction "Gate_1") (pintype "passive"))
      (node (ref "R14") (pin "2") (pinfunction "2_2") (pintype "passive"))
      (node (ref "R8") (pin "1") (pinfunction "1_1") (pintype "passive"))
    )
    (net (code "21") (name "Net-(D7-Anode)") (class "Default")
      (node (ref "D7") (pin "2") (pinfunction "Anode_2") (pintype "passive"))
      (node (ref "Q11") (pin "3") (pinfunction "Drain_3") (pintype "passive"))
      (node (ref "R11") (pin "1") (pinfunction "1_1") (pintype "passive"))
    )
    (net (code "22") (name "Net-(D7-Cathode)") (class "Default")
      (node (ref "D7") (pin "1") (pinfunction "Cathode_1") (pintype "passive"))
      (node (ref "D8") (pin "1") (pinfunction "Cathode_1") (pintype "passive"))
      (node (ref "FB2") (pin "2") (pinfunction "2_2") (pintype "passive"))
      (node (ref "R13") (pin "1") (pinfunction "1_1") (pintype "passive"))
    )
    (net (code "23") (name "Net-(D9-Cathode)") (class "Default")
      (node (ref "D9") (pin "1") (pinfunction "Cathode_1") (pintype "passive"))
      (node (ref "R14") (pin "1") (pinfunction "1_1") (pintype "passive"))
    )
    (net (code "24") (name "Net-(FB1-Pad2)") (class "Default")
      (node (ref "FB1") (pin "2") (pinfunction "2_2") (pintype "passive"))
      (node (ref "R12") (pin "1") (pinfunction "1_1") (pintype "passive"))
    )
    (net (code "25") (name "Net-(Q1-Source)") (class "Default")
      (node (ref "Q1") (pin "2") (pinfunction "Source_2") (pintype "passive"))
      (node (ref "R1") (pin "1") (pinfunction "1_1") (pintype "passive"))
      (node (ref "R2") (pin "1") (pinfunction "1_1") (pintype "passive"))
      (node (ref "R3") (pin "1") (pinfunction "1_1") (pintype "passive"))
      (node (ref "R4") (pin "1") (pinfunction "1_1") (pintype "passive"))
    )
    (net (code "26") (name "Net-(Q2-Source)") (class "Default")
      (node (ref "Q2") (pin "2") (pinfunction "Source_2") (pintype "passive"))
      (node (ref "R1") (pin "2") (pinfunction "2_2") (pintype "passive"))
      (node (ref "R2") (pin "2") (pinfunction "2_2") (pintype "passive"))
      (node (ref "R3") (pin "2") (pinfunction "2_2") (pintype "passive"))
      (node (ref "R5") (pin "1") (pinfunction "1_1") (pintype "passive"))
    )
    (net (code "27") (name "Net-(R10-Pad1)") (class "Default")
      (node (ref "R10") (pin "1") (pinfunction "1_1") (pintype "passive"))
      (node (ref "R13") (pin "2") (pinfunction "2_2") (pintype "passive"))
    )
    (net (code "28") (name "Net-(R12-Pad2)") (class "Default")
      (node (ref "R12") (pin "2") (pinfunction "2_2") (pintype "passive"))
      (node (ref "R9") (pin "1") (pinfunction "1_1") (pintype "passive"))
    )
    (net (code "29") (name "Net-(R20-Pad2)") (class "Default")
      (node (ref "R20") (pin "2") (pinfunction "2_2") (pintype "passive"))
      (node (ref "R21") (pin "1") (pinfunction "1_1") (pintype "passive"))
    )
    (net (code "30") (name "Net-(R22-Pad2)") (class "Default")
      (node (ref "R22") (pin "2") (pinfunction "2_2") (pintype "passive"))
      (node (ref "R23") (pin "1") (pinfunction "1_1") (pintype "passive"))
    )
    (net (code "31") (name "VBAT") (class "Default")
      (node (ref "C1") (pin "1") (pinfunction "1_1") (pintype "passive"))
      (node (ref "C3") (pin "2") (pinfunction "2_2") (pintype "passive"))
      (node (ref "D1") (pin "1") (pinfunction "1_1") (pintype "passive"))
      (node (ref "D3") (pin "1") (pinfunction "Cathode_1") (pintype "passive"))
      (node (ref "D4") (pin "2") (pinfunction "Anode_2") (pintype "passive"))
      (node (ref "Q1") (pin "3") (pinfunction "Drain_3") (pintype "passive"))
      (node (ref "Q1") (pin "4") (pinfunction "Drain_4") (pintype "passive"))
      (node (ref "Q3") (pin "2") (pinfunction "Source_2") (pintype "passive"))
      (node (ref "Q3") (pin "3") (pinfunction "Source_3") (pintype "passive"))
      (node (ref "Q3") (pin "4") (pinfunction "Source_4") (pintype "passive"))
      (node (ref "Q3") (pin "5") (pinfunction "Source_5") (pintype "passive"))
      (node (ref "Q3") (pin "6") (pinfunction "Source_6") (pintype "passive"))
      (node (ref "Q3") (pin "7") (pinfunction "Source_7") (pintype "passive"))
      (node (ref "Q3") (pin "8") (pinfunction "Source_8") (pintype "passive"))
      (node (ref "Q42") (pin "2") (pinfunction "Source_2") (pintype "passive"))
      (node (ref "Q42") (pin "3") (pinfunction "Source_3") (pintype "passive"))
      (node (ref "Q42") (pin "4") (pinfunction "Source_4") (pintype "passive"))
      (node (ref "Q42") (pin "5") (pinfunction "Source_5") (pintype "passive"))
      (node (ref "Q42") (pin "6") (pinfunction "Source_6") (pintype "passive"))
      (node (ref "Q42") (pin "7") (pinfunction "Source_7") (pintype "passive"))
      (node (ref "Q42") (pin "8") (pinfunction "Source_8") (pintype "passive"))
      (node (ref "Q5") (pin "2") (pinfunction "Source_2") (pintype "passive"))
      (node (ref "Q5") (pin "3") (pinfunction "Source_3") (pintype "passive"))
      (node (ref "Q5") (pin "4") (pinfunction "Source_4") (pintype "passive"))
      (node (ref "Q5") (pin "5") (pinfunction "Source_5") (pintype "passive"))
      (node (ref "Q5") (pin "6") (pinfunction "Source_6") (pintype "passive"))
      (node (ref "Q5") (pin "7") (pinfunction "Source_7") (pintype "passive"))
      (node (ref "Q5") (pin "8") (pinfunction "Source_8") (pintype "passive"))
      (node (ref "Q52") (pin "2") (pinfunction "Source_2") (pintype "passive"))
      (node (ref "Q52") (pin "3") (pinfunction "Source_3") (pintype "passive"))
      (node (ref "Q52") (pin "4") (pinfunction "Source_4") (pintype "passive"))
      (node (ref "Q52") (pin "5") (pinfunction "Source_5") (pintype "passive"))
      (node (ref "Q52") (pin "6") (pinfunction "Source_6") (pintype "passive"))
      (node (ref "Q52") (pin "7") (pinfunction "Source_7") (pintype "passive"))
      (node (ref "Q52") (pin "8") (pinfunction "Source_8") (pintype "passive"))
      (node (ref "Q53") (pin "2") (pinfunction "Source_2") (pintype "passive"))
      (node (ref "Q53") (pin "3") (pinfunction "Source_3") (pintype "passive"))
      (node (ref "Q53") (pin "4") (pinfunction "Source_4") (pintype "passive"))
      (node (ref "Q53") (pin "5") (pinfunction "Source_5") (pintype "passive"))
      (node (ref "Q53") (pin "6") (pinfunction "Source_6") (pintype "passive"))
      (node (ref "Q53") (pin "7") (pinfunction "Source_7") (pintype "passive"))
      (node (ref "Q53") (pin "8") (pinfunction "Source_8") (pintype "passive"))
      (node (ref "Q56") (pin "2") (pinfunction "Source_2") (pintype "passive"))
      (node (ref "Q56") (pin "3") (pinfunction "Source_3") (pintype "passive"))
      (node (ref "Q56") (pin "4") (pinfunction "Source_4") (pintype "passive"))
      (node (ref "Q56") (pin "5") (pinfunction "Source_5") (pintype "passive"))
      (node (ref "Q56") (pin "6") (pinfunction "Source_6") (pintype "passive"))
      (node (ref "Q56") (pin "7") (pinfunction "Source_7") (pintype "passive"))
      (node (ref "Q56") (pin "8") (pinfunction "Source_8") (pintype "passive"))
      (node (ref "Q7") (pin "2") (pinfunction "Source_2") (pintype "passive"))
      (node (ref "Q7") (pin "3") (pinfunction "Source_3") (pintype "passive"))
      (node (ref "Q7") (pin "4") (pinfunction "Source_4") (pintype "passive"))
      (node (ref "Q7") (pin "5") (pinfunction "Source_5") (pintype "passive"))
      (node (ref "Q7") (pin "6") (pinfunction "Source_6") (pintype "passive"))
      (node (ref "Q7") (pin "7") (pinfunction "Source_7") (pintype "passive"))
      (node (ref "Q7") (pin "8") (pinfunction "Source_8") (pintype "passive"))
      (node (ref "Q9") (pin "2") (pinfunction "Source_2") (pintype "passive"))
      (node (ref "Q9") (pin "3") (pinfunction "Source_3") (pintype "passive"))
      (node (ref "Q9") (pin "4") (pinfunction "Source_4") (pintype "passive"))
      (node (ref "Q9") (pin "5") (pinfunction "Source_5") (pintype "passive"))
      (node (ref "Q9") (pin "6") (pinfunction "Source_6") (pintype "passive"))
      (node (ref "Q9") (pin "7") (pinfunction "Source_7") (pintype "passive"))
      (node (ref "Q9") (pin "8") (pinfunction "Source_8") (pintype "passive"))
      (node (ref "R6") (pin "1") (pinfunction "1_1") (pintype "passive"))
      (node (ref "T1") (pin "1") (pinfunction "1_1") (pintype "passive"))
    )
    (net (code "32") (name "unconnected-(MT1-Pad1)") (class "Default")
      (node (ref "MT1") (pin "1") (pinfunction "1_1") (pintype "passive+no_connect"))
    )
    (net (code "33") (name "unconnected-(MT2-Pad1)") (class "Default")
      (node (ref "MT2") (pin "1") (pinfunction "1_1") (pintype "passive+no_connect"))
    )
    (net (code "34") (name "unconnected-(MT3-Pad1)") (class "Default")
      (node (ref "MT3") (pin "1") (pinfunction "1_1") (pintype "passive+no_connect"))
    )
    (net (code "35") (name "unconnected-(MT4-Pad1)") (class "Default")
      (node (ref "MT4") (pin "1") (pinfunction "1_1") (pintype "passive+no_connect"))
    )
  )
)
